# Dev.net
KiCad netlist of a schematic drawn in Altium Designer
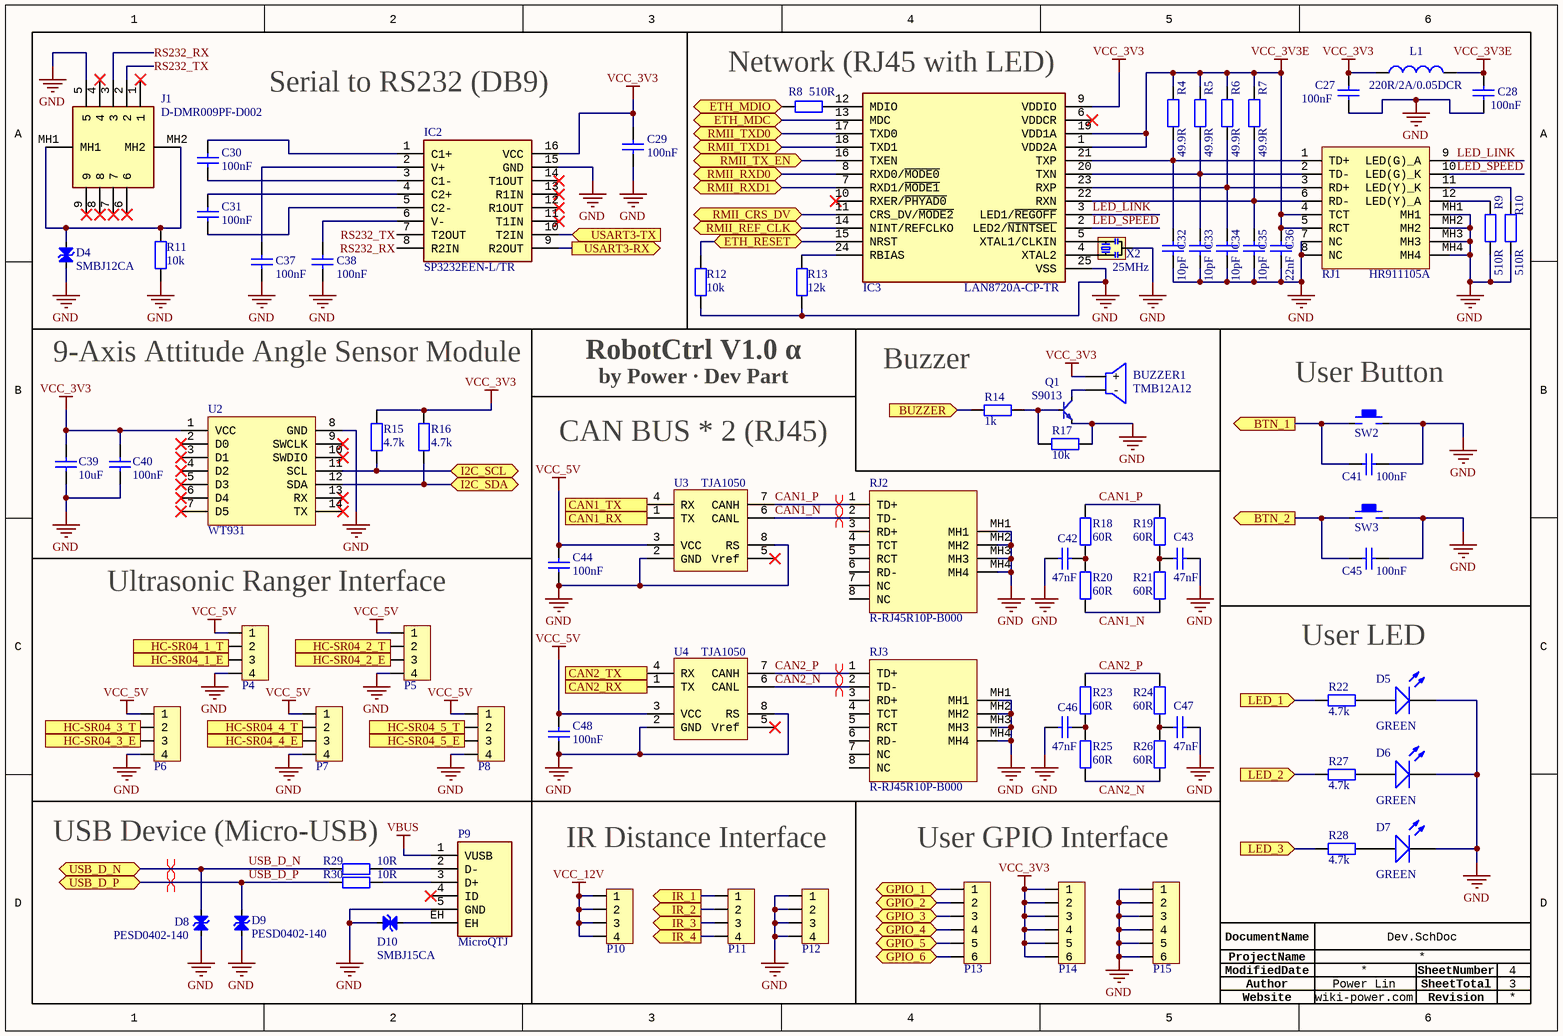
[diagram p0: Dev.SchDoc]

(export (version "E")
  (design (tool "Eeschema 10.0.6"))
  (components
    (comp (ref "BUZZER1")
      (value "TMB12A12")
      (footprint "DIP,P=7.6mm")
      (description "TMB12A12 有源蜂鸣器")
      (libsource (lib "Power_Lib_Altium") (part "BUZZER"))
    )
    (comp (ref "C27")
      (value "100nF")
      (footprint "CAP-0603")
      (description "贴片电容")
      (libsource (lib "Power_Lib_Altium") (part "CAP"))
    )
    (comp (ref "C28")
      (value "100nF")
      (footprint "CAP-0603")
      (description "贴片电容")
      (libsource (lib "Power_Lib_Altium") (part "CAP"))
    )
    (comp (ref "C29")
      (value "100nF")
      (footprint "CAP-0603")
      (description "贴片电容")
      (libsource (lib "Power_Lib_Altium") (part "CAP"))
    )
    (comp (ref "C30")
      (value "100nF")
      (footprint "CAP-0603")
      (description "贴片电容")
      (libsource (lib "Power_Lib_Altium") (part "CAP"))
    )
    (comp (ref "C31")
      (value "100nF")
      (footprint "CAP-0603")
      (description "贴片电容")
      (libsource (lib "Power_Lib_Altium") (part "CAP"))
    )
    (comp (ref "C32")
      (value "10pF")
      (footprint "CAP-0603")
      (description "贴片电容")
      (libsource (lib "Power_Lib_Altium") (part "CAP"))
    )
    (comp (ref "C33")
      (value "10pF")
      (footprint "CAP-0603")
      (description "贴片电容")
      (libsource (lib "Power_Lib_Altium") (part "CAP"))
    )
    (comp (ref "C34")
      (value "10pF")
      (footprint "CAP-0603")
      (description "贴片电容")
      (libsource (lib "Power_Lib_Altium") (part "CAP"))
    )
    (comp (ref "C35")
      (value "10pF")
      (footprint "CAP-0603")
      (description "贴片电容")
      (libsource (lib "Power_Lib_Altium") (part "CAP"))
    )
    (comp (ref "C36")
      (value "22nF")
      (footprint "CAP-0603")
      (description "贴片电容")
      (libsource (lib "Power_Lib_Altium") (part "CAP"))
    )
    (comp (ref "C37")
      (value "100nF")
      (footprint "CAP-0603")
      (description "贴片电容")
      (libsource (lib "Power_Lib_Altium") (part "CAP"))
    )
    (comp (ref "C38")
      (value "100nF")
      (footprint "CAP-0603")
      (description "贴片电容")
      (libsource (lib "Power_Lib_Altium") (part "CAP"))
    )
    (comp (ref "C39")
      (value "10uF")
      (footprint "CAP-0603")
      (description "贴片电容")
      (libsource (lib "Power_Lib_Altium") (part "CAP"))
    )
    (comp (ref "C40")
      (value "100nF")
      (footprint "CAP-0603")
      (description "贴片电容")
      (libsource (lib "Power_Lib_Altium") (part "CAP"))
    )
    (comp (ref "C41")
      (value "100nF")
      (footprint "CAP-0603")
      (description "贴片电容")
      (libsource (lib "Power_Lib_Altium") (part "CAP"))
    )
    (comp (ref "C42")
      (value "47nF")
      (footprint "CAP-0603")
      (description "贴片电容")
      (libsource (lib "Power_Lib_Altium") (part "CAP"))
    )
    (comp (ref "C43")
      (value "47nF")
      (footprint "CAP-0603")
      (description "贴片电容")
      (libsource (lib "Power_Lib_Altium") (part "CAP"))
    )
    (comp (ref "C44")
      (value "100nF")
      (footprint "CAP-0603")
      (description "贴片电容")
      (libsource (lib "Power_Lib_Altium") (part "CAP"))
    )
    (comp (ref "C45")
      (value "100nF")
      (footprint "CAP-0603")
      (description "贴片电容")
      (libsource (lib "Power_Lib_Altium") (part "CAP"))
    )
    (comp (ref "C46")
      (value "47nF")
      (footprint "CAP-0603")
      (description "贴片电容")
      (libsource (lib "Power_Lib_Altium") (part "CAP"))
    )
    (comp (ref "C47")
      (value "47nF")
      (footprint "CAP-0603")
      (description "贴片电容")
      (libsource (lib "Power_Lib_Altium") (part "CAP"))
    )
    (comp (ref "C48")
      (value "100nF")
      (footprint "CAP-0603")
      (description "贴片电容")
      (libsource (lib "Power_Lib_Altium") (part "CAP"))
    )
    (comp (ref "D4")
      (value "SMBJ12CA")
      (footprint "DO-214AA/SMB")
      (libsource (lib "Power_Lib_Altium") (part "TVS_C"))
    )
    (comp (ref "D5")
      (value "GREEN")
      (footprint "LED-0603")
      (description "发光二极管")
      (libsource (lib "Power_Lib_Altium") (part "LED"))
    )
    (comp (ref "D6")
      (value "GREEN")
      (footprint "LED-0603")
      (description "发光二极管")
      (libsource (lib "Power_Lib_Altium") (part "LED"))
    )
    (comp (ref "D7")
      (value "GREEN")
      (footprint "LED-0603")
      (description "发光二极管")
      (libsource (lib "Power_Lib_Altium") (part "LED"))
    )
    (comp (ref "D8")
      (value "PESD0402-140")
      (footprint "D-0402")
      (libsource (lib "Power_Lib_Altium") (part "TVS_C"))
    )
    (comp (ref "D9")
      (value "PESD0402-140")
      (footprint "D-0402")
      (libsource (lib "Power_Lib_Altium") (part "TVS_C"))
    )
    (comp (ref "D10")
      (value "SMBJ15CA")
      (footprint "DO-214AA/SMB")
      (libsource (lib "Power_Lib_Altium") (part "TVS_C"))
    )
    (comp (ref "IC2")
      (value "SP3232EEN-L/TR")
      (footprint "SOIC-16_150mil")
      (description "RS232 芯片")
      (fields (field (name "MOUSER PART NUMBER") "701-SP3232EEN-L/TR"))
      (libsource (lib "Power_Lib_Altium") (part "SP3232EEN"))
    )
    (comp (ref "IC3")
      (value "LAN8720A-CP-TR")
      (footprint "QFN-24-4x4")
      (description "Ethernet ICs RMII 10/100 ETH XCVR w/HP AutoMDIXSupport")
      (fields (field (name "MOUSER PART NUMBER") "886-LAN8720A-CP-TR"))
      (libsource (lib "Power_Lib_Altium") (part "LAN8720A-CP-TR"))
    )
    (comp (ref "J1")
      (value "D-DMR009PF-D002")
      (footprint "Through Hole,P=2.77mm")
      (description "D-Sub 连接器")
      (fields
        (field (name "MANUFACTURER_PART_NUMBER") "5747844-5")
        (field (name "MOUSER PART NUMBER") "571-5747844-5")
      )
      (libsource (lib "Power_Lib_Altium") (part "DB9"))
    )
    (comp (ref "L1")
      (value "220R/2A/0.05DCR")
      (footprint "L-0603")
      (description "BLM18KG221SN1D")
      (libsource (lib "Power_Lib_Altium") (part "BEAD"))
    )
    (comp (ref "P4")
      (value "HDR1x4_2.54")
      (footprint "HDR1x4_2.54_180")
      (description "Header")
      (libsource (lib "Power_Lib_Altium") (part "HDR1x4_2.54"))
    )
    (comp (ref "P5")
      (value "HDR1x4_2.54")
      (footprint "HDR1x4_2.54_180")
      (description "Header")
      (libsource (lib "Power_Lib_Altium") (part "HDR1x4_2.54"))
    )
    (comp (ref "P6")
      (value "HDR1x4_2.54")
      (footprint "HDR1x4_2.54_180")
      (description "Header")
      (libsource (lib "Power_Lib_Altium") (part "HDR1x4_2.54"))
    )
    (comp (ref "P7")
      (value "HDR1x4_2.54")
      (footprint "HDR1x4_2.54_180")
      (description "Header")
      (libsource (lib "Power_Lib_Altium") (part "HDR1x4_2.54"))
    )
    (comp (ref "P8")
      (value "HDR1x4_2.54")
      (footprint "HDR1x4_2.54_180")
      (description "Header")
      (libsource (lib "Power_Lib_Altium") (part "HDR1x4_2.54"))
    )
    (comp (ref "P9")
      (value "MicroQTJ")
      (footprint "USB-MICRO")
      (description "USB_MICRO")
      (libsource (lib "Power_Lib_Altium") (part "USB_MICRO"))
    )
    (comp (ref "P10")
      (value "HDR1x4_2.54")
      (footprint "HDR1x4_2.54_180")
      (description "Header")
      (libsource (lib "Power_Lib_Altium") (part "HDR1x4_2.54"))
    )
    (comp (ref "P11")
      (value "HDR1x4_2.54")
      (footprint "HDR1x4_2.54_180")
      (description "Header")
      (libsource (lib "Power_Lib_Altium") (part "HDR1x4_2.54"))
    )
    (comp (ref "P12")
      (value "HDR1x4_2.54")
      (footprint "HDR1x4_2.54_180")
      (description "Header")
      (libsource (lib "Power_Lib_Altium") (part "HDR1x4_2.54"))
    )
    (comp (ref "P13")
      (value "HDR1x6")
      (footprint "HDR1X6_2.54_180")
      (description "Header")
      (libsource (lib "Power_Lib_Altium") (part "HDR1x6_2.54"))
    )
    (comp (ref "P14")
      (value "HDR1x6")
      (footprint "HDR1X6_2.54_180")
      (description "Header")
      (libsource (lib "Power_Lib_Altium") (part "HDR1x6_2.54"))
    )
    (comp (ref "P15")
      (value "HDR1x6")
      (footprint "HDR1X6_2.54_180")
      (description "Header")
      (libsource (lib "Power_Lib_Altium") (part "HDR1x6_2.54"))
    )
    (comp (ref "Q1")
      (value "S9013")
      (footprint "SOT-23-3")
      (libsource (lib "Power_Lib_Altium") (part "BJT_NPN"))
    )
    (comp (ref "R4")
      (value "49.9R")
      (footprint "R-0603")
      (description "贴片电阻")
      (libsource (lib "") (part "RES_3"))
    )
    (comp (ref "R5")
      (value "49.9R")
      (footprint "R-0603")
      (description "贴片电阻")
      (libsource (lib "") (part "RES_3"))
    )
    (comp (ref "R6")
      (value "49.9R")
      (footprint "R-0603")
      (description "贴片电阻")
      (libsource (lib "") (part "RES_3"))
    )
    (comp (ref "R7")
      (value "49.9R")
      (footprint "R-0603")
      (description "贴片电阻")
      (libsource (lib "") (part "RES_3"))
    )
    (comp (ref "R8")
      (value "510R")
      (footprint "R-0603")
      (description "贴片电阻")
      (libsource (lib "") (part "RES_2"))
    )
    (comp (ref "R9")
      (value "510R")
      (footprint "R-0603")
      (description "贴片电阻")
      (libsource (lib "") (part "RES_3"))
    )
    (comp (ref "R10")
      (value "510R")
      (footprint "R-0603")
      (description "贴片电阻")
      (libsource (lib "") (part "RES_3"))
    )
    (comp (ref "R11")
      (value "10k")
      (footprint "R-0603")
      (description "贴片电阻")
      (libsource (lib "") (part "RES_3"))
    )
    (comp (ref "R12")
      (value "10k")
      (footprint "R-0603")
      (description "贴片电阻")
      (libsource (lib "Power_Lib_Altium") (part "RES"))
    )
    (comp (ref "R13")
      (value "12k")
      (footprint "R-0603")
      (description "贴片电阻")
      (libsource (lib "Power_Lib_Altium") (part "RES"))
    )
    (comp (ref "R14")
      (value "1k")
      (footprint "R-0603")
      (description "贴片电阻")
      (libsource (lib "") (part "RES_1"))
    )
    (comp (ref "R15")
      (value "4.7k")
      (footprint "R-0603")
      (description "贴片电阻")
      (libsource (lib "") (part "RES_3"))
    )
    (comp (ref "R16")
      (value "4.7k")
      (footprint "R-0603")
      (description "贴片电阻")
      (libsource (lib "") (part "RES_3"))
    )
    (comp (ref "R17")
      (value "10k")
      (footprint "R-0603")
      (description "贴片电阻")
      (libsource (lib "") (part "RES_2"))
    )
    (comp (ref "R18")
      (value "60R")
      (footprint "R-0603")
      (description "贴片电阻")
      (libsource (lib "Power_Lib_Altium") (part "RES"))
    )
    (comp (ref "R19")
      (value "60R")
      (footprint "R-0603")
      (description "贴片电阻")
      (libsource (lib "") (part "RES_3"))
    )
    (comp (ref "R20")
      (value "60R")
      (footprint "R-0603")
      (description "贴片电阻")
      (libsource (lib "Power_Lib_Altium") (part "RES"))
    )
    (comp (ref "R21")
      (value "60R")
      (footprint "R-0603")
      (description "贴片电阻")
      (libsource (lib "") (part "RES_3"))
    )
    (comp (ref "R22")
      (value "4.7k")
      (footprint "R-0603")
      (description "贴片电阻")
      (libsource (lib "") (part "RES_2"))
    )
    (comp (ref "R23")
      (value "60R")
      (footprint "R-0603")
      (description "贴片电阻")
      (libsource (lib "Power_Lib_Altium") (part "RES"))
    )
    (comp (ref "R24")
      (value "60R")
      (footprint "R-0603")
      (description "贴片电阻")
      (libsource (lib "") (part "RES_3"))
    )
    (comp (ref "R25")
      (value "60R")
      (footprint "R-0603")
      (description "贴片电阻")
      (libsource (lib "Power_Lib_Altium") (part "RES"))
    )
    (comp (ref "R26")
      (value "60R")
      (footprint "R-0603")
      (description "贴片电阻")
      (libsource (lib "") (part "RES_3"))
    )
    (comp (ref "R27")
      (value "4.7k")
      (footprint "R-0603")
      (description "贴片电阻")
      (libsource (lib "") (part "RES_2"))
    )
    (comp (ref "R28")
      (value "4.7k")
      (footprint "R-0603")
      (description "贴片电阻")
      (libsource (lib "") (part "RES_2"))
    )
    (comp (ref "R29")
      (value "10R")
      (footprint "R-0603")
      (description "贴片电阻")
      (libsource (lib "") (part "RES_1"))
    )
    (comp (ref "R30")
      (value "10R")
      (footprint "R-0603")
      (description "贴片电阻")
      (libsource (lib "") (part "RES_1"))
    )
    (comp (ref "RJ1")
      (value "HR911105A")
      (footprint "HR911105A")
      (libsource (lib "Power_Lib_Altium") (part "RJ45_LED"))
    )
    (comp (ref "RJ2")
      (value "R-RJ45R10P-B000")
      (footprint "RRJ45R10PB000")
      (libsource (lib "Power_Lib_Altium") (part "RJ45"))
    )
    (comp (ref "RJ3")
      (value "R-RJ45R10P-B000")
      (footprint "RRJ45R10PB000")
      (libsource (lib "Power_Lib_Altium") (part "RJ45"))
    )
    (comp (ref "SW2")
      (value "KEY")
      (footprint "KEY-4P-4.2*3.4*2.5")
      (description "按键开关")
      (libsource (lib "Power_Lib_Altium") (part "KEY"))
    )
    (comp (ref "SW3")
      (value "KEY")
      (footprint "KEY-4P-4.2*3.4*2.5")
      (description "按键开关")
      (libsource (lib "Power_Lib_Altium") (part "KEY"))
    )
    (comp (ref "U2")
      (value "WT931")
      (footprint "WT931")
      (description "陀螺仪模组")
      (libsource (lib "Power_Lib_Altium") (part "WT931"))
    )
    (comp (ref "U3")
      (value "TJA1050")
      (footprint "SOIC_8")
      (description "CAN 控制器（5V）")
      (libsource (lib "Power_Lib_Altium") (part "TJA1050"))
    )
    (comp (ref "U4")
      (value "TJA1050")
      (footprint "SOIC_8")
      (description "CAN 控制器（5V）")
      (libsource (lib "Power_Lib_Altium") (part "TJA1050"))
    )
    (comp (ref "X2")
      (value "25MHz")
      (footprint "SMD3213-3P")
      (description "CSTCE25M00G51-R0")
      (libsource (lib "Power_Lib_Altium") (part "XTAL"))
    )
  )
  (nets
    (net (code "1") (name "/BTN_1") (class "Default")
      (node (ref "C41") (pin "2") (pinfunction "2_2") (pintype "passive"))
      (node (ref "SW2") (pin "1") (pinfunction "1_1") (pintype "passive"))
    )
    (net (code "2") (name "/BTN_2") (class "Default")
      (node (ref "C45") (pin "2") (pinfunction "2_2") (pintype "passive"))
      (node (ref "SW3") (pin "1") (pinfunction "1_1") (pintype "passive"))
    )
    (net (code "3") (name "/BUZZER") (class "Default")
      (node (ref "R14") (pin "1") (pinfunction "1_1") (pintype "passive"))
    )
    (net (code "4") (name "/CAN1_N") (class "Default")
      (node (ref "R20") (pin "2") (pinfunction "2_2") (pintype "passive"))
      (node (ref "R21") (pin "1") (pinfunction "1_1") (pintype "passive"))
      (node (ref "RJ2") (pin "2") (pinfunction "TD-_2") (pintype "passive"))
      (node (ref "U3") (pin "6") (pinfunction "CANL_6") (pintype "passive"))
    )
    (net (code "5") (name "/CAN1_P") (class "Default")
      (node (ref "R18") (pin "1") (pinfunction "1_1") (pintype "passive"))
      (node (ref "R19") (pin "2") (pinfunction "2_2") (pintype "passive"))
      (node (ref "RJ2") (pin "1") (pinfunction "TD+_1") (pintype "passive"))
      (node (ref "U3") (pin "7") (pinfunction "CANH_7") (pintype "passive"))
    )
    (net (code "6") (name "/CAN1_RX") (class "Default")
      (node (ref "U3") (pin "1") (pinfunction "TX_1") (pintype "passive"))
    )
    (net (code "7") (name "/CAN1_TX") (class "Default")
      (node (ref "U3") (pin "4") (pinfunction "RX_4") (pintype "passive"))
    )
    (net (code "8") (name "/CAN2_N") (class "Default")
      (node (ref "R25") (pin "2") (pinfunction "2_2") (pintype "passive"))
      (node (ref "R26") (pin "1") (pinfunction "1_1") (pintype "passive"))
      (node (ref "RJ3") (pin "2") (pinfunction "TD-_2") (pintype "passive"))
      (node (ref "U4") (pin "6") (pinfunction "CANL_6") (pintype "passive"))
    )
    (net (code "9") (name "/CAN2_P") (class "Default")
      (node (ref "R23") (pin "1") (pinfunction "1_1") (pintype "passive"))
      (node (ref "R24") (pin "2") (pinfunction "2_2") (pintype "passive"))
      (node (ref "RJ3") (pin "1") (pinfunction "TD+_1") (pintype "passive"))
      (node (ref "U4") (pin "7") (pinfunction "CANH_7") (pintype "passive"))
    )
    (net (code "10") (name "/CAN2_RX") (class "Default")
      (node (ref "U4") (pin "1") (pinfunction "TX_1") (pintype "passive"))
    )
    (net (code "11") (name "/CAN2_TX") (class "Default")
      (node (ref "U4") (pin "4") (pinfunction "RX_4") (pintype "passive"))
    )
    (net (code "12") (name "/ETH_MDC") (class "Default")
      (node (ref "IC3") (pin "13") (pinfunction "MDC_13") (pintype "passive"))
    )
    (net (code "13") (name "/ETH_MDIO") (class "Default")
      (node (ref "R8") (pin "2") (pinfunction "2_2") (pintype "passive"))
    )
    (net (code "14") (name "/ETH_RESET") (class "Default")
      (node (ref "IC3") (pin "15") (pinfunction "NRST_15") (pintype "passive"))
      (node (ref "R12") (pin "1") (pinfunction "1_1") (pintype "passive"))
    )
    (net (code "15") (name "/GPIO_1") (class "Default")
      (node (ref "P13") (pin "1") (pinfunction "1_1") (pintype "passive"))
    )
    (net (code "16") (name "/GPIO_2") (class "Default")
      (node (ref "P13") (pin "2") (pinfunction "2_2") (pintype "passive"))
    )
    (net (code "17") (name "/GPIO_3") (class "Default")
      (node (ref "P13") (pin "3") (pinfunction "3_3") (pintype "passive"))
    )
    (net (code "18") (name "/GPIO_4") (class "Default")
      (node (ref "P13") (pin "4") (pinfunction "4_4") (pintype "passive"))
    )
    (net (code "19") (name "/GPIO_5") (class "Default")
      (node (ref "P13") (pin "5") (pinfunction "5_5") (pintype "passive"))
    )
    (net (code "20") (name "/GPIO_6") (class "Default")
      (node (ref "P13") (pin "6") (pinfunction "6_6") (pintype "passive"))
    )
    (net (code "21") (name "/HC-SR04_1_E") (class "Default")
      (node (ref "P4") (pin "3") (pinfunction "3_3") (pintype "passive"))
    )
    (net (code "22") (name "/HC-SR04_1_T") (class "Default")
      (node (ref "P4") (pin "2") (pinfunction "2_2") (pintype "passive"))
    )
    (net (code "23") (name "/HC-SR04_2_E") (class "Default")
      (node (ref "P5") (pin "3") (pinfunction "3_3") (pintype "passive"))
    )
    (net (code "24") (name "/HC-SR04_2_T") (class "Default")
      (node (ref "P5") (pin "2") (pinfunction "2_2") (pintype "passive"))
    )
    (net (code "25") (name "/HC-SR04_3_E") (class "Default")
      (node (ref "P6") (pin "3") (pinfunction "3_3") (pintype "passive"))
    )
    (net (code "26") (name "/HC-SR04_3_T") (class "Default")
      (node (ref "P6") (pin "2") (pinfunction "2_2") (pintype "passive"))
    )
    (net (code "27") (name "/HC-SR04_4_E") (class "Default")
      (node (ref "P7") (pin "3") (pinfunction "3_3") (pintype "passive"))
    )
    (net (code "28") (name "/HC-SR04_4_T") (class "Default")
      (node (ref "P7") (pin "2") (pinfunction "2_2") (pintype "passive"))
    )
    (net (code "29") (name "/HC-SR04_5_E") (class "Default")
      (node (ref "P8") (pin "3") (pinfunction "3_3") (pintype "passive"))
    )
    (net (code "30") (name "/HC-SR04_5_T") (class "Default")
      (node (ref "P8") (pin "2") (pinfunction "2_2") (pintype "passive"))
    )
    (net (code "31") (name "/I2C_SCL") (class "Default")
      (node (ref "R15") (pin "1") (pinfunction "1_1") (pintype "passive"))
      (node (ref "U2") (pin "11") (pinfunction "SCL_11") (pintype "passive"))
    )
    (net (code "32") (name "/I2C_SDA") (class "Default")
      (node (ref "R16") (pin "1") (pinfunction "1_1") (pintype "passive"))
      (node (ref "U2") (pin "12") (pinfunction "SDA_12") (pintype "passive"))
    )
    (net (code "33") (name "/IR_1") (class "Default")
      (node (ref "P11") (pin "1") (pinfunction "1_1") (pintype "passive"))
    )
    (net (code "34") (name "/IR_2") (class "Default")
      (node (ref "P11") (pin "2") (pinfunction "2_2") (pintype "passive"))
    )
    (net (code "35") (name "/IR_3") (class "Default")
      (node (ref "P11") (pin "3") (pinfunction "3_3") (pintype "passive"))
    )
    (net (code "36") (name "/IR_4") (class "Default")
      (node (ref "P11") (pin "4") (pinfunction "4_4") (pintype "passive"))
    )
    (net (code "37") (name "/LED_1") (class "Default")
      (node (ref "R22") (pin "2") (pinfunction "2_2") (pintype "passive"))
    )
    (net (code "38") (name "/LED_2") (class "Default")
      (node (ref "R27") (pin "2") (pinfunction "2_2") (pintype "passive"))
    )
    (net (code "39") (name "/LED_3") (class "Default")
      (node (ref "R28") (pin "2") (pinfunction "2_2") (pintype "passive"))
    )
    (net (code "40") (name "/LED_LINK") (class "Default")
      (node (ref "IC3") (pin "3") (pinfunction "LED1/~{REGOFF}_3") (pintype "passive"))
      (node (ref "RJ1") (pin "9") (pinfunction "LED(G)_A_9") (pintype "passive"))
    )
    (net (code "41") (name "/LED_SPEED") (class "Default")
      (node (ref "IC3") (pin "2") (pinfunction "LED2/~{NINTSEL}_2") (pintype "passive"))
      (node (ref "RJ1") (pin "10") (pinfunction "LED(G)_K_10") (pintype "passive"))
    )
    (net (code "42") (name "/RMII_CRS_DV") (class "Default")
      (node (ref "IC3") (pin "11") (pinfunction "CRS_DV/~{MODE2}_11") (pintype "passive"))
    )
    (net (code "43") (name "/RMII_REF_CLK") (class "Default")
      (node (ref "IC3") (pin "14") (pinfunction "NINT/REFCLKO_14") (pintype "passive"))
    )
    (net (code "44") (name "/RMII_RXD0") (class "Default")
      (node (ref "IC3") (pin "8") (pinfunction "RXD0/~{MODE0}_8") (pintype "passive"))
    )
    (net (code "45") (name "/RMII_RXD1") (class "Default")
      (node (ref "IC3") (pin "7") (pinfunction "RXD1/~{MODE1}_7") (pintype "passive"))
    )
    (net (code "46") (name "/RMII_TXD0") (class "Default")
      (node (ref "IC3") (pin "17") (pinfunction "TXD0_17") (pintype "passive"))
    )
    (net (code "47") (name "/RMII_TXD1") (class "Default")
      (node (ref "IC3") (pin "18") (pinfunction "TXD1_18") (pintype "passive"))
    )
    (net (code "48") (name "/RMII_TX_EN") (class "Default")
      (node (ref "IC3") (pin "16") (pinfunction "TXEN_16") (pintype "passive"))
    )
    (net (code "49") (name "/RS232_RX") (class "Default")
      (node (ref "IC2") (pin "8") (pinfunction "R2IN_8") (pintype "passive"))
      (node (ref "J1") (pin "3") (pinfunction "3_3") (pintype "passive"))
    )
    (net (code "50") (name "/RS232_TX") (class "Default")
      (node (ref "IC2") (pin "7") (pinfunction "T2OUT_7") (pintype "passive"))
      (node (ref "J1") (pin "2") (pinfunction "2_2") (pintype "passive"))
    )
    (net (code "51") (name "/USART3-RX") (class "Default")
      (node (ref "IC2") (pin "9") (pinfunction "R2OUT_9") (pintype "passive"))
    )
    (net (code "52") (name "/USART3-TX") (class "Default")
      (node (ref "IC2") (pin "10") (pinfunction "T2IN_10") (pintype "passive"))
    )
    (net (code "53") (name "/USB_D_N") (class "Default")
      (node (ref "D8") (pin "2") (pinfunction "2_2") (pintype "passive"))
      (node (ref "R29") (pin "1") (pinfunction "1_1") (pintype "passive"))
    )
    (net (code "54") (name "/USB_D_P") (class "Default")
      (node (ref "D9") (pin "2") (pinfunction "2_2") (pintype "passive"))
      (node (ref "R30") (pin "1") (pinfunction "1_1") (pintype "passive"))
    )
    (net (code "55") (name "GND") (class "Default")
      (node (ref "C27") (pin "1") (pinfunction "1_1") (pintype "passive"))
      (node (ref "C28") (pin "1") (pinfunction "1_1") (pintype "passive"))
      (node (ref "C29") (pin "1") (pinfunction "1_1") (pintype "passive"))
      (node (ref "C32") (pin "1") (pinfunction "1_1") (pintype "passive"))
      (node (ref "C33") (pin "1") (pinfunction "1_1") (pintype "passive"))
      (node (ref "C34") (pin "1") (pinfunction "1_1") (pintype "passive"))
      (node (ref "C35") (pin "1") (pinfunction "1_1") (pintype "passive"))
      (node (ref "C36") (pin "1") (pinfunction "1_1") (pintype "passive"))
      (node (ref "C37") (pin "1") (pinfunction "1_1") (pintype "passive"))
      (node (ref "C38") (pin "1") (pinfunction "1_1") (pintype "passive"))
      (node (ref "C39") (pin "2") (pinfunction "2_2") (pintype "passive"))
      (node (ref "C40") (pin "2") (pinfunction "2_2") (pintype "passive"))
      (node (ref "C41") (pin "1") (pinfunction "1_1") (pintype "passive"))
      (node (ref "C42") (pin "2") (pinfunction "2_2") (pintype "passive"))
      (node (ref "C43") (pin "2") (pinfunction "2_2") (pintype "passive"))
      (node (ref "C44") (pin "1") (pinfunction "1_1") (pintype "passive"))
      (node (ref "C45") (pin "1") (pinfunction "1_1") (pintype "passive"))
      (node (ref "C46") (pin "2") (pinfunction "2_2") (pintype "passive"))
      (node (ref "C47") (pin "2") (pinfunction "2_2") (pintype "passive"))
      (node (ref "C48") (pin "1") (pinfunction "1_1") (pintype "passive"))
      (node (ref "D10") (pin "2") (pinfunction "2_2") (pintype "passive"))
      (node (ref "D4") (pin "1") (pinfunction "1_1") (pintype "passive"))
      (node (ref "D5") (pin "K") (pinfunction "K_K") (pintype "passive"))
      (node (ref "D6") (pin "K") (pinfunction "K_K") (pintype "passive"))
      (node (ref "D7") (pin "K") (pinfunction "K_K") (pintype "passive"))
      (node (ref "D8") (pin "1") (pinfunction "1_1") (pintype "passive"))
      (node (ref "D9") (pin "1") (pinfunction "1_1") (pintype "passive"))
      (node (ref "IC2") (pin "15") (pinfunction "GND_15") (pintype "passive"))
      (node (ref "IC3") (pin "25") (pinfunction "VSS_25") (pintype "passive"))
      (node (ref "J1") (pin "5") (pinfunction "5_5") (pintype "passive"))
      (node (ref "P12") (pin "1") (pinfunction "1_1") (pintype "passive"))
      (node (ref "P12") (pin "2") (pinfunction "2_2") (pintype "passive"))
      (node (ref "P12") (pin "3") (pinfunction "3_3") (pintype "passive"))
      (node (ref "P12") (pin "4") (pinfunction "4_4") (pintype "passive"))
      (node (ref "P15") (pin "1") (pinfunction "1_1") (pintype "passive"))
      (node (ref "P15") (pin "2") (pinfunction "2_2") (pintype "passive"))
      (node (ref "P15") (pin "3") (pinfunction "3_3") (pintype "passive"))
      (node (ref "P15") (pin "4") (pinfunction "4_4") (pintype "passive"))
      (node (ref "P15") (pin "5") (pinfunction "5_5") (pintype "passive"))
      (node (ref "P15") (pin "6") (pinfunction "6_6") (pintype "passive"))
      (node (ref "P4") (pin "4") (pinfunction "4_4") (pintype "passive"))
      (node (ref "P5") (pin "4") (pinfunction "4_4") (pintype "passive"))
      (node (ref "P6") (pin "4") (pinfunction "4_4") (pintype "passive"))
      (node (ref "P7") (pin "4") (pinfunction "4_4") (pintype "passive"))
      (node (ref "P8") (pin "4") (pinfunction "4_4") (pintype "passive"))
      (node (ref "P9") (pin "5") (pinfunction "GND_5") (pintype "passive"))
      (node (ref "Q1") (pin "2") (pinfunction "E_2") (pintype "passive"))
      (node (ref "R10") (pin "1") (pinfunction "1_1") (pintype "passive"))
      (node (ref "R11") (pin "1") (pinfunction "1_1") (pintype "passive"))
      (node (ref "R12") (pin "2") (pinfunction "2_2") (pintype "passive"))
      (node (ref "R13") (pin "2") (pinfunction "2_2") (pintype "passive"))
      (node (ref "R17") (pin "1") (pinfunction "1_1") (pintype "passive"))
      (node (ref "R9") (pin "1") (pinfunction "1_1") (pintype "passive"))
      (node (ref "RJ1") (pin "7") (pinfunction "NC_7") (pintype "passive"))
      (node (ref "RJ1") (pin "8") (pinfunction "NC_8") (pintype "passive"))
      (node (ref "RJ1") (pin "MH1") (pinfunction "MH1_MH1") (pintype "passive"))
      (node (ref "RJ1") (pin "MH2") (pinfunction "MH2_MH2") (pintype "passive"))
      (node (ref "RJ1") (pin "MH3") (pinfunction "MH3_MH3") (pintype "passive"))
      (node (ref "RJ1") (pin "MH4") (pinfunction "MH4_MH4") (pintype "passive"))
      (node (ref "RJ2") (pin "MH1") (pinfunction "MH1_MH1") (pintype "passive"))
      (node (ref "RJ2") (pin "MH2") (pinfunction "MH2_MH2") (pintype "passive"))
      (node (ref "RJ2") (pin "MH3") (pinfunction "MH3_MH3") (pintype "passive"))
      (node (ref "RJ2") (pin "MH4") (pinfunction "MH4_MH4") (pintype "passive"))
      (node (ref "RJ3") (pin "MH1") (pinfunction "MH1_MH1") (pintype "passive"))
      (node (ref "RJ3") (pin "MH2") (pinfunction "MH2_MH2") (pintype "passive"))
      (node (ref "RJ3") (pin "MH3") (pinfunction "MH3_MH3") (pintype "passive"))
      (node (ref "RJ3") (pin "MH4") (pinfunction "MH4_MH4") (pintype "passive"))
      (node (ref "SW2") (pin "2") (pinfunction "2_2") (pintype "passive"))
      (node (ref "SW3") (pin "2") (pinfunction "2_2") (pintype "passive"))
      (node (ref "U2") (pin "8") (pinfunction "GND_8") (pintype "passive"))
      (node (ref "U3") (pin "2") (pinfunction "GND_2") (pintype "passive"))
      (node (ref "U3") (pin "8") (pinfunction "RS_8") (pintype "passive"))
      (node (ref "U4") (pin "2") (pinfunction "GND_2") (pintype "passive"))
      (node (ref "U4") (pin "8") (pinfunction "RS_8") (pintype "passive"))
      (node (ref "X2") (pin "2") (pinfunction "GND_2") (pintype "passive"))
    )
    (net (code "56") (name "Net-(BUZZER1--)") (class "Default")
      (node (ref "BUZZER1") (pin "2") (pinfunction "-_2") (pintype "passive"))
      (node (ref "Q1") (pin "3") (pinfunction "C_3") (pintype "passive"))
    )
    (net (code "57") (name "Net-(C42-Pad1)") (class "Default")
      (node (ref "C42") (pin "1") (pinfunction "1_1") (pintype "passive"))
      (node (ref "R18") (pin "2") (pinfunction "2_2") (pintype "passive"))
      (node (ref "R20") (pin "1") (pinfunction "1_1") (pintype "passive"))
    )
    (net (code "58") (name "Net-(C43-Pad1)") (class "Default")
      (node (ref "C43") (pin "1") (pinfunction "1_1") (pintype "passive"))
      (node (ref "R19") (pin "1") (pinfunction "1_1") (pintype "passive"))
      (node (ref "R21") (pin "2") (pinfunction "2_2") (pintype "passive"))
    )
    (net (code "59") (name "Net-(C46-Pad1)") (class "Default")
      (node (ref "C46") (pin "1") (pinfunction "1_1") (pintype "passive"))
      (node (ref "R23") (pin "2") (pinfunction "2_2") (pintype "passive"))
      (node (ref "R25") (pin "1") (pinfunction "1_1") (pintype "passive"))
    )
    (net (code "60") (name "Net-(C47-Pad1)") (class "Default")
      (node (ref "C47") (pin "1") (pinfunction "1_1") (pintype "passive"))
      (node (ref "R24") (pin "1") (pinfunction "1_1") (pintype "passive"))
      (node (ref "R26") (pin "2") (pinfunction "2_2") (pintype "passive"))
    )
    (net (code "61") (name "Net-(D4-Pad2)") (class "Default")
      (node (ref "D4") (pin "2") (pinfunction "2_2") (pintype "passive"))
      (node (ref "J1") (pin "MH1") (pinfunction "MH1_MH1") (pintype "passive"))
      (node (ref "J1") (pin "MH2") (pinfunction "MH2_MH2") (pintype "passive"))
      (node (ref "R11") (pin "2") (pinfunction "2_2") (pintype "passive"))
    )
    (net (code "62") (name "Net-(D5-PadA)") (class "Default")
      (node (ref "D5") (pin "A") (pinfunction "A_A") (pintype "passive"))
      (node (ref "R22") (pin "1") (pinfunction "1_1") (pintype "passive"))
    )
    (net (code "63") (name "Net-(D6-PadA)") (class "Default")
      (node (ref "D6") (pin "A") (pinfunction "A_A") (pintype "passive"))
      (node (ref "R27") (pin "1") (pinfunction "1_1") (pintype "passive"))
    )
    (net (code "64") (name "Net-(D7-PadA)") (class "Default")
      (node (ref "D7") (pin "A") (pinfunction "A_A") (pintype "passive"))
      (node (ref "R28") (pin "1") (pinfunction "1_1") (pintype "passive"))
    )
    (net (code "65") (name "Net-(D10-Pad1)") (class "Default")
      (node (ref "D10") (pin "1") (pinfunction "1_1") (pintype "passive"))
      (node (ref "P9") (pin "EH") (pinfunction "EH_EH") (pintype "passive"))
    )
    (net (code "66") (name "Net-(IC2-C1+)") (class "Default")
      (node (ref "C30") (pin "2") (pinfunction "2_2") (pintype "passive"))
      (node (ref "IC2") (pin "1") (pinfunction "C1+_1") (pintype "passive"))
    )
    (net (code "67") (name "Net-(IC2-C1-)") (class "Default")
      (node (ref "C30") (pin "1") (pinfunction "1_1") (pintype "passive"))
      (node (ref "IC2") (pin "3") (pinfunction "C1-_3") (pintype "passive"))
    )
    (net (code "68") (name "Net-(IC2-C2+)") (class "Default")
      (node (ref "C31") (pin "2") (pinfunction "2_2") (pintype "passive"))
      (node (ref "IC2") (pin "4") (pinfunction "C2+_4") (pintype "passive"))
    )
    (net (code "69") (name "Net-(IC2-C2-)") (class "Default")
      (node (ref "C31") (pin "1") (pinfunction "1_1") (pintype "passive"))
      (node (ref "IC2") (pin "5") (pinfunction "C2-_5") (pintype "passive"))
    )
    (net (code "70") (name "Net-(IC2-V+)") (class "Default")
      (node (ref "C37") (pin "2") (pinfunction "2_2") (pintype "passive"))
      (node (ref "IC2") (pin "2") (pinfunction "V+_2") (pintype "passive"))
    )
    (net (code "71") (name "Net-(IC2-V-)") (class "Default")
      (node (ref "C38") (pin "2") (pinfunction "2_2") (pintype "passive"))
      (node (ref "IC2") (pin "6") (pinfunction "V-_6") (pintype "passive"))
    )
    (net (code "72") (name "Net-(IC3-MDIO)") (class "Default")
      (node (ref "IC3") (pin "12") (pinfunction "MDIO_12") (pintype "passive"))
      (node (ref "R8") (pin "1") (pinfunction "1_1") (pintype "passive"))
    )
    (net (code "73") (name "Net-(IC3-RBIAS)") (class "Default")
      (node (ref "IC3") (pin "24") (pinfunction "RBIAS_24") (pintype "passive"))
      (node (ref "R13") (pin "1") (pinfunction "1_1") (pintype "passive"))
    )
    (net (code "74") (name "Net-(IC3-RXN)") (class "Default")
      (node (ref "C35") (pin "2") (pinfunction "2_2") (pintype "passive"))
      (node (ref "IC3") (pin "22") (pinfunction "RXN_22") (pintype "passive"))
      (node (ref "R7") (pin "1") (pinfunction "1_1") (pintype "passive"))
      (node (ref "RJ1") (pin "6") (pinfunction "RD-_6") (pintype "passive"))
    )
    (net (code "75") (name "Net-(IC3-RXP)") (class "Default")
      (node (ref "C34") (pin "2") (pinfunction "2_2") (pintype "passive"))
      (node (ref "IC3") (pin "23") (pinfunction "RXP_23") (pintype "passive"))
      (node (ref "R6") (pin "1") (pinfunction "1_1") (pintype "passive"))
      (node (ref "RJ1") (pin "3") (pinfunction "RD+_3") (pintype "passive"))
    )
    (net (code "76") (name "Net-(IC3-TXN)") (class "Default")
      (node (ref "C33") (pin "2") (pinfunction "2_2") (pintype "passive"))
      (node (ref "IC3") (pin "20") (pinfunction "TXN_20") (pintype "passive"))
      (node (ref "R5") (pin "1") (pinfunction "1_1") (pintype "passive"))
      (node (ref "RJ1") (pin "2") (pinfunction "TD-_2") (pintype "passive"))
    )
    (net (code "77") (name "Net-(IC3-TXP)") (class "Default")
      (node (ref "C32") (pin "2") (pinfunction "2_2") (pintype "passive"))
      (node (ref "IC3") (pin "21") (pinfunction "TXP_21") (pintype "passive"))
      (node (ref "R4") (pin "1") (pinfunction "1_1") (pintype "passive"))
      (node (ref "RJ1") (pin "1") (pinfunction "TD+_1") (pintype "passive"))
    )
    (net (code "78") (name "Net-(IC3-XTAL1{slash}CLKIN)") (class "Default")
      (node (ref "IC3") (pin "5") (pinfunction "XTAL1/CLKIN_5") (pintype "passive"))
      (node (ref "X2") (pin "3") (pinfunction "OSC2_3") (pintype "passive"))
    )
    (net (code "79") (name "Net-(IC3-XTAL2)") (class "Default")
      (node (ref "IC3") (pin "4") (pinfunction "XTAL2_4") (pintype "passive"))
      (node (ref "X2") (pin "1") (pinfunction "OSC1_1") (pintype "passive"))
    )
    (net (code "80") (name "Net-(P9-D+)") (class "Default")
      (node (ref "P9") (pin "3") (pinfunction "D+_3") (pintype "passive"))
      (node (ref "R30") (pin "2") (pinfunction "2_2") (pintype "passive"))
    )
    (net (code "81") (name "Net-(P9-D-)") (class "Default")
      (node (ref "P9") (pin "2") (pinfunction "D-_2") (pintype "passive"))
      (node (ref "R29") (pin "2") (pinfunction "2_2") (pintype "passive"))
    )
    (net (code "82") (name "Net-(Q1-B)") (class "Default")
      (node (ref "Q1") (pin "1") (pinfunction "B_1") (pintype "passive"))
      (node (ref "R14") (pin "2") (pinfunction "2_2") (pintype "passive"))
      (node (ref "R17") (pin "2") (pinfunction "2_2") (pintype "passive"))
    )
    (net (code "83") (name "Net-(RJ1-LED(Y)_A)") (class "Default")
      (node (ref "R9") (pin "2") (pinfunction "2_2") (pintype "passive"))
      (node (ref "RJ1") (pin "12") (pinfunction "LED(Y)_A_12") (pintype "passive"))
    )
    (net (code "84") (name "Net-(RJ1-LED(Y)_K)") (class "Default")
      (node (ref "R10") (pin "2") (pinfunction "2_2") (pintype "passive"))
      (node (ref "RJ1") (pin "11") (pinfunction "LED(Y)_K_11") (pintype "passive"))
    )
    (net (code "85") (name "VBUS") (class "Default")
      (node (ref "P9") (pin "1") (pinfunction "VUSB_1") (pintype "passive"))
    )
    (net (code "86") (name "VCC_3V3") (class "Default")
      (node (ref "BUZZER1") (pin "1") (pinfunction "+_1") (pintype "passive"))
      (node (ref "C27") (pin "2") (pinfunction "2_2") (pintype "passive"))
      (node (ref "C29") (pin "2") (pinfunction "2_2") (pintype "passive"))
      (node (ref "C39") (pin "1") (pinfunction "1_1") (pintype "passive"))
      (node (ref "C40") (pin "1") (pinfunction "1_1") (pintype "passive"))
      (node (ref "IC2") (pin "16") (pinfunction "VCC_16") (pintype "passive"))
      (node (ref "IC3") (pin "9") (pinfunction "VDDIO_9") (pintype "passive"))
      (node (ref "L1") (pin "1") (pinfunction "1_1") (pintype "passive"))
      (node (ref "P14") (pin "1") (pinfunction "1_1") (pintype "passive"))
      (node (ref "P14") (pin "2") (pinfunction "2_2") (pintype "passive"))
      (node (ref "P14") (pin "3") (pinfunction "3_3") (pintype "passive"))
      (node (ref "P14") (pin "4") (pinfunction "4_4") (pintype "passive"))
      (node (ref "P14") (pin "5") (pinfunction "5_5") (pintype "passive"))
      (node (ref "P14") (pin "6") (pinfunction "6_6") (pintype "passive"))
      (node (ref "R15") (pin "2") (pinfunction "2_2") (pintype "passive"))
      (node (ref "R16") (pin "2") (pinfunction "2_2") (pintype "passive"))
      (node (ref "U2") (pin "1") (pinfunction "VCC_1") (pintype "passive"))
    )
    (net (code "87") (name "VCC_3V3E") (class "Default")
      (node (ref "C28") (pin "2") (pinfunction "2_2") (pintype "passive"))
      (node (ref "C36") (pin "2") (pinfunction "2_2") (pintype "passive"))
      (node (ref "IC3") (pin "1") (pinfunction "VDD2A_1") (pintype "passive"))
      (node (ref "IC3") (pin "19") (pinfunction "VDD1A_19") (pintype "passive"))
      (node (ref "L1") (pin "2") (pinfunction "2_2") (pintype "passive"))
      (node (ref "R4") (pin "2") (pinfunction "2_2") (pintype "passive"))
      (node (ref "R5") (pin "2") (pinfunction "2_2") (pintype "passive"))
      (node (ref "R6") (pin "2") (pinfunction "2_2") (pintype "passive"))
      (node (ref "R7") (pin "2") (pinfunction "2_2") (pintype "passive"))
      (node (ref "RJ1") (pin "4") (pinfunction "TCT_4") (pintype "passive"))
      (node (ref "RJ1") (pin "5") (pinfunction "RCT_5") (pintype "passive"))
    )
    (net (code "88") (name "VCC_5V") (class "Default")
      (node (ref "C44") (pin "2") (pinfunction "2_2") (pintype "passive"))
      (node (ref "C48") (pin "2") (pinfunction "2_2") (pintype "passive"))
      (node (ref "P4") (pin "1") (pinfunction "1_1") (pintype "passive"))
      (node (ref "P5") (pin "1") (pinfunction "1_1") (pintype "passive"))
      (node (ref "P6") (pin "1") (pinfunction "1_1") (pintype "passive"))
      (node (ref "P7") (pin "1") (pinfunction "1_1") (pintype "passive"))
      (node (ref "P8") (pin "1") (pinfunction "1_1") (pintype "passive"))
      (node (ref "U3") (pin "3") (pinfunction "VCC_3") (pintype "passive"))
      (node (ref "U4") (pin "3") (pinfunction "VCC_3") (pintype "passive"))
    )
    (net (code "89") (name "VCC_12V") (class "Default")
      (node (ref "P10") (pin "1") (pinfunction "1_1") (pintype "passive"))
      (node (ref "P10") (pin "2") (pinfunction "2_2") (pintype "passive"))
      (node (ref "P10") (pin "3") (pinfunction "3_3") (pintype "passive"))
      (node (ref "P10") (pin "4") (pinfunction "4_4") (pintype "passive"))
    )
    (net (code "90") (name "unconnected-(IC2-R1IN-Pad13)") (class "Default")
      (node (ref "IC2") (pin "13") (pinfunction "R1IN_13") (pintype "passive+no_connect"))
    )
    (net (code "91") (name "unconnected-(IC2-R1OUT-Pad12)") (class "Default")
      (node (ref "IC2") (pin "12") (pinfunction "R1OUT_12") (pintype "passive+no_connect"))
    )
    (net (code "92") (name "unconnected-(IC2-T1IN-Pad11)") (class "Default")
      (node (ref "IC2") (pin "11") (pinfunction "T1IN_11") (pintype "passive+no_connect"))
    )
    (net (code "93") (name "unconnected-(IC2-T1OUT-Pad14)") (class "Default")
      (node (ref "IC2") (pin "14") (pinfunction "T1OUT_14") (pintype "passive+no_connect"))
    )
    (net (code "94") (name "unconnected-(IC3-RXER{slash}~{PHYAD0}-Pad10)") (class "Default")
      (node (ref "IC3") (pin "10") (pinfunction "RXER/~{PHYAD0}_10") (pintype "passive+no_connect"))
    )
    (net (code "95") (name "unconnected-(IC3-VDDCR-Pad6)") (class "Default")
      (node (ref "IC3") (pin "6") (pinfunction "VDDCR_6") (pintype "passive+no_connect"))
    )
    (net (code "96") (name "unconnected-(J1-Pad1)") (class "Default")
      (node (ref "J1") (pin "1") (pinfunction "1_1") (pintype "passive+no_connect"))
    )
    (net (code "97") (name "unconnected-(J1-Pad4)") (class "Default")
      (node (ref "J1") (pin "4") (pinfunction "4_4") (pintype "passive+no_connect"))
    )
    (net (code "98") (name "unconnected-(J1-Pad6)") (class "Default")
      (node (ref "J1") (pin "6") (pinfunction "6_6") (pintype "passive+no_connect"))
    )
    (net (code "99") (name "unconnected-(J1-Pad7)") (class "Default")
      (node (ref "J1") (pin "7") (pinfunction "7_7") (pintype "passive+no_connect"))
    )
    (net (code "100") (name "unconnected-(J1-Pad8)") (class "Default")
      (node (ref "J1") (pin "8") (pinfunction "8_8") (pintype "passive+no_connect"))
    )
    (net (code "101") (name "unconnected-(J1-Pad9)") (class "Default")
      (node (ref "J1") (pin "9") (pinfunction "9_9") (pintype "passive+no_connect"))
    )
    (net (code "102") (name "unconnected-(P9-ID-Pad4)") (class "Default")
      (node (ref "P9") (pin "4") (pinfunction "ID_4") (pintype "passive+no_connect"))
    )
    (net (code "103") (name "unconnected-(RJ2-NC-Pad7)") (class "Default")
      (node (ref "RJ2") (pin "7") (pinfunction "NC_7") (pintype "passive"))
    )
    (net (code "104") (name "unconnected-(RJ2-NC-Pad8)") (class "Default")
      (node (ref "RJ2") (pin "8") (pinfunction "NC_8") (pintype "passive"))
    )
    (net (code "105") (name "unconnected-(RJ2-RCT-Pad5)") (class "Default")
      (node (ref "RJ2") (pin "5") (pinfunction "RCT_5") (pintype "passive"))
    )
    (net (code "106") (name "unconnected-(RJ2-RD+-Pad3)") (class "Default")
      (node (ref "RJ2") (pin "3") (pinfunction "RD+_3") (pintype "passive"))
    )
    (net (code "107") (name "unconnected-(RJ2-RD--Pad6)") (class "Default")
      (node (ref "RJ2") (pin "6") (pinfunction "RD-_6") (pintype "passive"))
    )
    (net (code "108") (name "unconnected-(RJ2-TCT-Pad4)") (class "Default")
      (node (ref "RJ2") (pin "4") (pinfunction "TCT_4") (pintype "passive"))
    )
    (net (code "109") (name "unconnected-(RJ3-NC-Pad7)") (class "Default")
      (node (ref "RJ3") (pin "7") (pinfunction "NC_7") (pintype "passive"))
    )
    (net (code "110") (name "unconnected-(RJ3-NC-Pad8)") (class "Default")
      (node (ref "RJ3") (pin "8") (pinfunction "NC_8") (pintype "passive"))
    )
    (net (code "111") (name "unconnected-(RJ3-RCT-Pad5)") (class "Default")
      (node (ref "RJ3") (pin "5") (pinfunction "RCT_5") (pintype "passive"))
    )
    (net (code "112") (name "unconnected-(RJ3-RD+-Pad3)") (class "Default")
      (node (ref "RJ3") (pin "3") (pinfunction "RD+_3") (pintype "passive"))
    )
    (net (code "113") (name "unconnected-(RJ3-RD--Pad6)") (class "Default")
      (node (ref "RJ3") (pin "6") (pinfunction "RD-_6") (pintype "passive"))
    )
    (net (code "114") (name "unconnected-(RJ3-TCT-Pad4)") (class "Default")
      (node (ref "RJ3") (pin "4") (pinfunction "TCT_4") (pintype "passive"))
    )
    (net (code "115") (name "unconnected-(U2-D0-Pad2)") (class "Default")
      (node (ref "U2") (pin "2") (pinfunction "D0_2") (pintype "passive+no_connect"))
    )
    (net (code "116") (name "unconnected-(U2-D1-Pad3)") (class "Default")
      (node (ref "U2") (pin "3") (pinfunction "D1_3") (pintype "passive+no_connect"))
    )
    (net (code "117") (name "unconnected-(U2-D2-Pad4)") (class "Default")
      (node (ref "U2") (pin "4") (pinfunction "D2_4") (pintype "passive+no_connect"))
    )
    (net (code "118") (name "unconnected-(U2-D3-Pad5)") (class "Default")
      (node (ref "U2") (pin "5") (pinfunction "D3_5") (pintype "passive+no_connect"))
    )
    (net (code "119") (name "unconnected-(U2-D4-Pad6)") (class "Default")
      (node (ref "U2") (pin "6") (pinfunction "D4_6") (pintype "passive+no_connect"))
    )
    (net (code "120") (name "unconnected-(U2-D5-Pad7)") (class "Default")
      (node (ref "U2") (pin "7") (pinfunction "D5_7") (pintype "passive+no_connect"))
    )
    (net (code "121") (name "unconnected-(U2-RX-Pad13)") (class "Default")
      (node (ref "U2") (pin "13") (pinfunction "RX_13") (pintype "passive+no_connect"))
    )
    (net (code "122") (name "unconnected-(U2-SWCLK-Pad9)") (class "Default")
      (node (ref "U2") (pin "9") (pinfunction "SWCLK_9") (pintype "passive+no_connect"))
    )
    (net (code "123") (name "unconnected-(U2-SWDIO-Pad10)") (class "Default")
      (node (ref "U2") (pin "10") (pinfunction "SWDIO_10") (pintype "passive+no_connect"))
    )
    (net (code "124") (name "unconnected-(U2-TX-Pad14)") (class "Default")
      (node (ref "U2") (pin "14") (pinfunction "TX_14") (pintype "passive+no_connect"))
    )
    (net (code "125") (name "unconnected-(U3-Vref-Pad5)") (class "Default")
      (node (ref "U3") (pin "5") (pinfunction "Vref_5") (pintype "passive+no_connect"))
    )
    (net (code "126") (name "unconnected-(U4-Vref-Pad5)") (class "Default")
      (node (ref "U4") (pin "5") (pinfunction "Vref_5") (pintype "passive+no_connect"))
    )
  )
)
